# MCU.net
KiCad netlist of a schematic drawn in Altium Designer
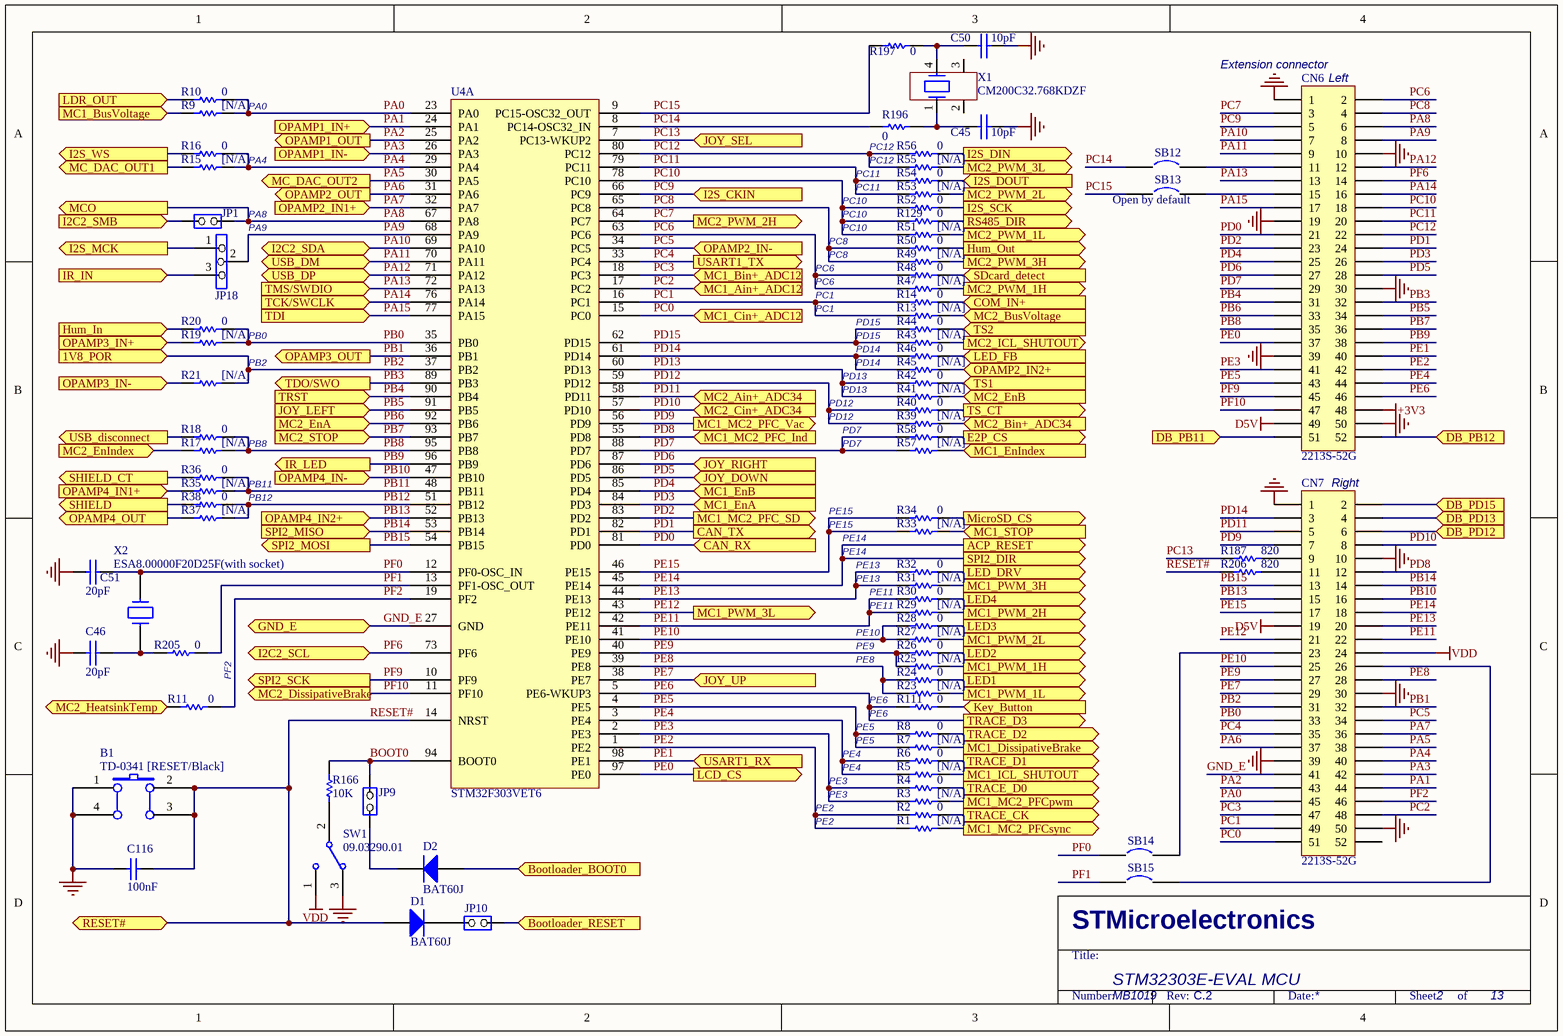
[diagram p0: MCU.SchDoc]

(export (version "E")
  (design (tool "Eeschema 10.0.6"))
  (components
    (comp (ref "B1")
      (value "TD-0341 [RESET/Black]")
      (footprint "PB10")
      (description "SE PUSHBUTTON")
      (libsource (lib "Documents") (part "SW PUSHBUTTON"))
    )
    (comp (ref "C45")
      (value "10pF")
      (footprint "0603C")
      (description "Capacitor")
      (libsource (lib "*") (part "CAP"))
    )
    (comp (ref "C46")
      (value "20pF")
      (footprint "0603C")
      (description "Capacitor")
      (libsource (lib "") (part "CAP_1"))
    )
    (comp (ref "C50")
      (value "10pF")
      (footprint "0603C")
      (description "Capacitor")
      (libsource (lib "*") (part "CAP"))
    )
    (comp (ref "C51")
      (value "20pF")
      (footprint "0603C")
      (description "Capacitor")
      (libsource (lib "") (part "CAP_1"))
    )
    (comp (ref "C116")
      (value "100nF")
      (footprint "0603C")
      (description "Capacitor")
      (fields (field (name "PUBLISHER") "Altium Limited"))
      (libsource (lib "Miscellaneous Devices") (part "CAP"))
    )
    (comp (ref "CN6")
      (value "2213S-52G")
      (footprint "2*26P")
      (description "Header, 26-Pin, Dual row")
      (fields (field (name "PUBLISHER") "Altium Limited"))
      (libsource (lib "MB1019") (part "Header 26X2_1"))
    )
    (comp (ref "CN7")
      (value "2213S-52G")
      (footprint "2*26P")
      (description "Header, 26-Pin, Dual row")
      (fields (field (name "PUBLISHER") "Altium Limited"))
      (libsource (lib "MB1019") (part "Header 26X2_1"))
    )
    (comp (ref "D1")
      (value "BAT60J")
      (footprint "SOD-323")
      (description "Default Diode")
      (fields (field (name "PUBLISHER") "Altium Limited"))
      (libsource (lib "Miscellaneous Devices") (part "Diode"))
    )
    (comp (ref "D2")
      (value "BAT60J")
      (footprint "SOD-323")
      (description "Default Diode")
      (fields (field (name "PUBLISHER") "Altium Limited"))
      (libsource (lib "Miscellaneous Devices") (part "Diode"))
    )
    (comp (ref "JP1") (value "~") (footprint "SIP2") (libsource (lib "*") (part "JP2")))
    (comp (ref "JP9") (value "~") (footprint "SIP2") (libsource (lib "*") (part "JP2")))
    (comp (ref "JP10") (value "~") (footprint "SIP2") (libsource (lib "*") (part "JP2")))
    (comp (ref "JP18") (value "~") (footprint "SIP3") (libsource (lib "STR910_SCHLIB") (part "Jumper3")))
    (comp (ref "R1")
      (value "[N/A]")
      (footprint "0603R")
      (description "Resistor")
      (fields (field (name "PUBLISHER") "Altium Limited"))
      (libsource (lib "Miscellaneous Devices") (part "Res1"))
    )
    (comp (ref "R2")
      (value "0")
      (footprint "0603R")
      (description "Resistor")
      (fields (field (name "PUBLISHER") "Altium Limited"))
      (libsource (lib "Miscellaneous Devices") (part "Res1"))
    )
    (comp (ref "R3")
      (value "[N/A]")
      (footprint "0603R")
      (description "Resistor")
      (fields (field (name "PUBLISHER") "Altium Limited"))
      (libsource (lib "Miscellaneous Devices") (part "Res1"))
    )
    (comp (ref "R4")
      (value "0")
      (footprint "0603R")
      (description "Resistor")
      (fields (field (name "PUBLISHER") "Altium Limited"))
      (libsource (lib "Miscellaneous Devices") (part "Res1"))
    )
    (comp (ref "R5")
      (value "[N/A]")
      (footprint "0603R")
      (description "Resistor")
      (fields (field (name "PUBLISHER") "Altium Limited"))
      (libsource (lib "Miscellaneous Devices") (part "Res1"))
    )
    (comp (ref "R6")
      (value "0")
      (footprint "0603R")
      (description "Resistor")
      (fields (field (name "PUBLISHER") "Altium Limited"))
      (libsource (lib "Miscellaneous Devices") (part "Res1"))
    )
    (comp (ref "R7")
      (value "[N/A]")
      (footprint "0603R")
      (description "Resistor")
      (fields (field (name "PUBLISHER") "Altium Limited"))
      (libsource (lib "Miscellaneous Devices") (part "Res1"))
    )
    (comp (ref "R8")
      (value "0")
      (footprint "0603R")
      (description "Resistor")
      (fields (field (name "PUBLISHER") "Altium Limited"))
      (libsource (lib "Miscellaneous Devices") (part "Res1"))
    )
    (comp (ref "R9")
      (value "[N/A]")
      (footprint "0603R")
      (description "Resistor")
      (fields (field (name "PUBLISHER") "Altium Limited"))
      (libsource (lib "Miscellaneous Devices") (part "Res1"))
    )
    (comp (ref "R10")
      (value "0")
      (footprint "0603R")
      (description "Resistor")
      (fields (field (name "PUBLISHER") "Altium Limited"))
      (libsource (lib "Miscellaneous Devices") (part "Res1"))
    )
    (comp (ref "R11")
      (value "0")
      (footprint "0603R")
      (description "Resistor")
      (fields (field (name "PUBLISHER") "Altium Limited"))
      (libsource (lib "Miscellaneous Devices") (part "Res1"))
    )
    (comp (ref "R13")
      (value "[N/A]")
      (footprint "0603R")
      (description "Resistor")
      (fields (field (name "PUBLISHER") "Altium Limited"))
      (libsource (lib "Miscellaneous Devices") (part "Res1"))
    )
    (comp (ref "R14")
      (value "0")
      (footprint "0603R")
      (description "Resistor")
      (fields (field (name "PUBLISHER") "Altium Limited"))
      (libsource (lib "Miscellaneous Devices") (part "Res1"))
    )
    (comp (ref "R15")
      (value "[N/A]")
      (footprint "0603R")
      (description "Resistor")
      (fields (field (name "PUBLISHER") "Altium Limited"))
      (libsource (lib "Miscellaneous Devices") (part "Res1"))
    )
    (comp (ref "R16")
      (value "0")
      (footprint "0603R")
      (description "Resistor")
      (fields (field (name "PUBLISHER") "Altium Limited"))
      (libsource (lib "Miscellaneous Devices") (part "Res1"))
    )
    (comp (ref "R17")
      (value "[N/A]")
      (footprint "0603R")
      (description "Resistor")
      (fields (field (name "PUBLISHER") "Altium Limited"))
      (libsource (lib "Miscellaneous Devices") (part "Res1"))
    )
    (comp (ref "R18")
      (value "0")
      (footprint "0603R")
      (description "Resistor")
      (fields (field (name "PUBLISHER") "Altium Limited"))
      (libsource (lib "Miscellaneous Devices") (part "Res1"))
    )
    (comp (ref "R19")
      (value "[N/A]")
      (footprint "0603R")
      (description "Resistor")
      (fields (field (name "PUBLISHER") "Altium Limited"))
      (libsource (lib "Miscellaneous Devices") (part "Res1"))
    )
    (comp (ref "R20")
      (value "0")
      (footprint "0603R")
      (description "Resistor")
      (fields (field (name "PUBLISHER") "Altium Limited"))
      (libsource (lib "Miscellaneous Devices") (part "Res1"))
    )
    (comp (ref "R21")
      (value "[N/A]")
      (footprint "0603R")
      (description "Resistor")
      (fields (field (name "PUBLISHER") "Altium Limited"))
      (libsource (lib "Miscellaneous Devices") (part "Res1"))
    )
    (comp (ref "R23")
      (value "[N/A]")
      (footprint "0603R")
      (description "Resistor")
      (fields (field (name "PUBLISHER") "Altium Limited"))
      (libsource (lib "Miscellaneous Devices") (part "Res1"))
    )
    (comp (ref "R24")
      (value "0")
      (footprint "0603R")
      (description "Resistor")
      (fields (field (name "PUBLISHER") "Altium Limited"))
      (libsource (lib "Miscellaneous Devices") (part "Res1"))
    )
    (comp (ref "R25")
      (value "[N/A]")
      (footprint "0603R")
      (description "Resistor")
      (fields (field (name "PUBLISHER") "Altium Limited"))
      (libsource (lib "Miscellaneous Devices") (part "Res1"))
    )
    (comp (ref "R26")
      (value "0")
      (footprint "0603R")
      (description "Resistor")
      (fields (field (name "PUBLISHER") "Altium Limited"))
      (libsource (lib "Miscellaneous Devices") (part "Res1"))
    )
    (comp (ref "R27")
      (value "[N/A]")
      (footprint "0603R")
      (description "Resistor")
      (fields (field (name "PUBLISHER") "Altium Limited"))
      (libsource (lib "Miscellaneous Devices") (part "Res1"))
    )
    (comp (ref "R28")
      (value "0")
      (footprint "0603R")
      (description "Resistor")
      (fields (field (name "PUBLISHER") "Altium Limited"))
      (libsource (lib "Miscellaneous Devices") (part "Res1"))
    )
    (comp (ref "R29")
      (value "[N/A]")
      (footprint "0603R")
      (description "Resistor")
      (fields (field (name "PUBLISHER") "Altium Limited"))
      (libsource (lib "Miscellaneous Devices") (part "Res1"))
    )
    (comp (ref "R30")
      (value "0")
      (footprint "0603R")
      (description "Resistor")
      (fields (field (name "PUBLISHER") "Altium Limited"))
      (libsource (lib "Miscellaneous Devices") (part "Res1"))
    )
    (comp (ref "R31")
      (value "[N/A]")
      (footprint "0603R")
      (description "Resistor")
      (fields (field (name "PUBLISHER") "Altium Limited"))
      (libsource (lib "Miscellaneous Devices") (part "Res1"))
    )
    (comp (ref "R32")
      (value "0")
      (footprint "0603R")
      (description "Resistor")
      (fields (field (name "PUBLISHER") "Altium Limited"))
      (libsource (lib "Miscellaneous Devices") (part "Res1"))
    )
    (comp (ref "R33")
      (value "[N/A]")
      (footprint "0603R")
      (description "Resistor")
      (fields (field (name "PUBLISHER") "Altium Limited"))
      (libsource (lib "Miscellaneous Devices") (part "Res1"))
    )
    (comp (ref "R34")
      (value "0")
      (footprint "0603R")
      (description "Resistor")
      (fields (field (name "PUBLISHER") "Altium Limited"))
      (libsource (lib "Miscellaneous Devices") (part "Res1"))
    )
    (comp (ref "R35")
      (value "[N/A]")
      (footprint "0603R")
      (description "Resistor")
      (fields (field (name "PUBLISHER") "Altium Limited"))
      (libsource (lib "Miscellaneous Devices") (part "Res1"))
    )
    (comp (ref "R36")
      (value "0")
      (footprint "0603R")
      (description "Resistor")
      (fields (field (name "PUBLISHER") "Altium Limited"))
      (libsource (lib "Miscellaneous Devices") (part "Res1"))
    )
    (comp (ref "R37")
      (value "[N/A]")
      (footprint "0603R")
      (description "Resistor")
      (fields (field (name "PUBLISHER") "Altium Limited"))
      (libsource (lib "Miscellaneous Devices") (part "Res1"))
    )
    (comp (ref "R38")
      (value "0")
      (footprint "0603R")
      (description "Resistor")
      (fields (field (name "PUBLISHER") "Altium Limited"))
      (libsource (lib "Miscellaneous Devices") (part "Res1"))
    )
    (comp (ref "R39")
      (value "[N/A]")
      (footprint "0603R")
      (description "Resistor")
      (fields (field (name "PUBLISHER") "Altium Limited"))
      (libsource (lib "Miscellaneous Devices") (part "Res1"))
    )
    (comp (ref "R40")
      (value "0")
      (footprint "0603R")
      (description "Resistor")
      (fields (field (name "PUBLISHER") "Altium Limited"))
      (libsource (lib "Miscellaneous Devices") (part "Res1"))
    )
    (comp (ref "R41")
      (value "[N/A]")
      (footprint "0603R")
      (description "Resistor")
      (fields (field (name "PUBLISHER") "Altium Limited"))
      (libsource (lib "Miscellaneous Devices") (part "Res1"))
    )
    (comp (ref "R42")
      (value "0")
      (footprint "0603R")
      (description "Resistor")
      (fields (field (name "PUBLISHER") "Altium Limited"))
      (libsource (lib "Miscellaneous Devices") (part "Res1"))
    )
    (comp (ref "R43")
      (value "[N/A]")
      (footprint "0603R")
      (description "Resistor")
      (fields (field (name "PUBLISHER") "Altium Limited"))
      (libsource (lib "Miscellaneous Devices") (part "Res1"))
    )
    (comp (ref "R44")
      (value "0")
      (footprint "0603R")
      (description "Resistor")
      (fields (field (name "PUBLISHER") "Altium Limited"))
      (libsource (lib "Miscellaneous Devices") (part "Res1"))
    )
    (comp (ref "R45")
      (value "[N/A]")
      (footprint "0603R")
      (description "Resistor")
      (fields (field (name "PUBLISHER") "Altium Limited"))
      (libsource (lib "Miscellaneous Devices") (part "Res1"))
    )
    (comp (ref "R46")
      (value "0")
      (footprint "0603R")
      (description "Resistor")
      (fields (field (name "PUBLISHER") "Altium Limited"))
      (libsource (lib "Miscellaneous Devices") (part "Res1"))
    )
    (comp (ref "R47")
      (value "[N/A]")
      (footprint "0603R")
      (description "Resistor")
      (fields (field (name "PUBLISHER") "Altium Limited"))
      (libsource (lib "Miscellaneous Devices") (part "Res1"))
    )
    (comp (ref "R48")
      (value "0")
      (footprint "0603R")
      (description "Resistor")
      (fields (field (name "PUBLISHER") "Altium Limited"))
      (libsource (lib "Miscellaneous Devices") (part "Res1"))
    )
    (comp (ref "R49")
      (value "[N/A]")
      (footprint "0603R")
      (description "Resistor")
      (fields (field (name "PUBLISHER") "Altium Limited"))
      (libsource (lib "Miscellaneous Devices") (part "Res1"))
    )
    (comp (ref "R50")
      (value "0")
      (footprint "0603R")
      (description "Resistor")
      (fields (field (name "PUBLISHER") "Altium Limited"))
      (libsource (lib "Miscellaneous Devices") (part "Res1"))
    )
    (comp (ref "R51")
      (value "[N/A]")
      (footprint "0603R")
      (description "Resistor")
      (fields (field (name "PUBLISHER") "Altium Limited"))
      (libsource (lib "Miscellaneous Devices") (part "Res1"))
    )
    (comp (ref "R52")
      (value "0")
      (footprint "0603R")
      (description "Resistor")
      (fields (field (name "PUBLISHER") "Altium Limited"))
      (libsource (lib "Miscellaneous Devices") (part "Res1"))
    )
    (comp (ref "R53")
      (value "[N/A]")
      (footprint "0603R")
      (description "Resistor")
      (fields (field (name "PUBLISHER") "Altium Limited"))
      (libsource (lib "Miscellaneous Devices") (part "Res1"))
    )
    (comp (ref "R54")
      (value "0")
      (footprint "0603R")
      (description "Resistor")
      (fields (field (name "PUBLISHER") "Altium Limited"))
      (libsource (lib "Miscellaneous Devices") (part "Res1"))
    )
    (comp (ref "R55")
      (value "[N/A]")
      (footprint "0603R")
      (description "Resistor")
      (fields (field (name "PUBLISHER") "Altium Limited"))
      (libsource (lib "Miscellaneous Devices") (part "Res1"))
    )
    (comp (ref "R56")
      (value "0")
      (footprint "0603R")
      (description "Resistor")
      (fields (field (name "PUBLISHER") "Altium Limited"))
      (libsource (lib "Miscellaneous Devices") (part "Res1"))
    )
    (comp (ref "R57")
      (value "[N/A]")
      (footprint "0603R")
      (description "Resistor")
      (fields (field (name "PUBLISHER") "Altium Limited"))
      (libsource (lib "Miscellaneous Devices") (part "Res1"))
    )
    (comp (ref "R58")
      (value "0")
      (footprint "0603R")
      (description "Resistor")
      (fields (field (name "PUBLISHER") "Altium Limited"))
      (libsource (lib "Miscellaneous Devices") (part "Res1"))
    )
    (comp (ref "R111")
      (value "0")
      (footprint "0603R")
      (description "Resistor")
      (fields (field (name "PUBLISHER") "Altium Limited"))
      (libsource (lib "Miscellaneous Devices") (part "Res1"))
    )
    (comp (ref "R129")
      (value "0")
      (footprint "0603R")
      (description "Resistor")
      (fields (field (name "PUBLISHER") "Altium Limited"))
      (libsource (lib "Miscellaneous Devices") (part "Res1"))
    )
    (comp (ref "R166")
      (value "10K")
      (footprint "0603R")
      (description "Resistor")
      (fields (field (name "PUBLISHER") "Altium Limited"))
      (libsource (lib "Miscellaneous Devices") (part "res1"))
    )
    (comp (ref "R187")
      (value "820")
      (footprint "0603R")
      (description "Resistor")
      (fields (field (name "PUBLISHER") "Altium Limited"))
      (libsource (lib "Miscellaneous Devices") (part "Res1"))
    )
    (comp (ref "R196")
      (value "0")
      (footprint "0603R")
      (description "Resistor")
      (fields (field (name "PUBLISHER") "Altium Limited"))
      (libsource (lib "Miscellaneous Devices") (part "Res1"))
    )
    (comp (ref "R197")
      (value "0")
      (footprint "0603R")
      (description "Resistor")
      (fields (field (name "PUBLISHER") "Altium Limited"))
      (libsource (lib "Miscellaneous Devices") (part "Res1"))
    )
    (comp (ref "R205")
      (value "0")
      (footprint "0603R")
      (description "Resistor")
      (fields (field (name "PUBLISHER") "Altium Limited"))
      (libsource (lib "Miscellaneous Devices") (part "Res1"))
    )
    (comp (ref "R206")
      (value "820")
      (footprint "0603R")
      (description "Resistor")
      (fields (field (name "PUBLISHER") "Altium Limited"))
      (libsource (lib "Miscellaneous Devices") (part "Res1"))
    )
    (comp (ref "SB12")
      (value "~")
      (footprint "JP2_SMD")
      (description "Circuit Breaker")
      (fields (field (name "PUBLISHER") "Altium Limited"))
      (libsource (lib "Miscellaneous Devices") (part "Circuit Breaker"))
    )
    (comp (ref "SB13")
      (value "~")
      (footprint "JP2_SMD")
      (description "Circuit Breaker")
      (fields (field (name "PUBLISHER") "Altium Limited"))
      (libsource (lib "Miscellaneous Devices") (part "Circuit Breaker"))
    )
    (comp (ref "SB14")
      (value "~")
      (footprint "JP2_SMD")
      (description "Circuit Breaker")
      (fields (field (name "PUBLISHER") "Altium Limited"))
      (libsource (lib "Miscellaneous Devices") (part "Circuit Breaker"))
    )
    (comp (ref "SB15")
      (value "~")
      (footprint "JP2_SMD")
      (description "Circuit Breaker")
      (fields (field (name "PUBLISHER") "Altium Limited"))
      (libsource (lib "Miscellaneous Devices") (part "Circuit Breaker"))
    )
    (comp (ref "SW1")
      (value "09.03290.01")
      (footprint "SIP3")
      (description "SPDT Subminiature Toggle Switch, Right Angle Mounting, Vertical Actuation")
      (fields (field (name "PUBLISHER") "Altium Limited"))
      (libsource (lib "Miscellaneous Devices") (part "SW-SPDT"))
    )
    (comp (ref "U4")
      (value "STM32F303VET6")
      (footprint "IC149-100-025-B5")
      (libsource (lib "MB1019") (part "STM32F303VCT6"))
    )
    (comp (ref "X1") (value "CM200C32.768KDZF") (footprint "SM8") (libsource (lib "*") (part "MC306")))
    (comp (ref "X2")
      (value "ESA8.00000F20D25F(with socket)")
      (footprint "XTAL_socket")
      (description "Crystal")
      (libsource (lib "*") (part "CRYSTAL"))
    )
  )
  (nets
    (net (code "1") (name "+3V3") (class "Default")
      (node (ref "CN6") (pin "48") (pinfunction "48_48") (pintype "passive"))
    )
    (net (code "2") (name "/BOOT0") (class "Default")
      (node (ref "JP9") (pin "2") (pinfunction "NO_2") (pintype "passive"))
      (node (ref "R166") (pin "1") (pinfunction "1_1") (pintype "passive"))
      (node (ref "U4") (pin "94") (pinfunction "BOOT0_94") (pintype "passive"))
    )
    (net (code "3") (name "/Bootloader_BOOT0") (class "Default")
      (node (ref "D2") (pin "1") (pinfunction "A_1") (pintype "passive"))
    )
    (net (code "4") (name "/Bootloader_RESET") (class "Default")
      (node (ref "JP10") (pin "2") (pinfunction "NO_2") (pintype "passive"))
    )
    (net (code "5") (name "/COM_IN+") (class "Default")
      (node (ref "R14") (pin "1") (pinfunction "1_1") (pintype "passive"))
    )
    (net (code "6") (name "/DB_PB11") (class "Default")
      (node (ref "CN6") (pin "51") (pinfunction "51_51") (pintype "passive"))
    )
    (net (code "7") (name "/DB_PB12") (class "Default")
      (node (ref "CN6") (pin "52") (pinfunction "52_52") (pintype "passive"))
    )
    (net (code "8") (name "/DB_PD12") (class "Default")
      (node (ref "CN7") (pin "6") (pinfunction "6_6") (pintype "passive"))
    )
    (net (code "9") (name "/DB_PD13") (class "Default")
      (node (ref "CN7") (pin "4") (pinfunction "4_4") (pintype "passive"))
    )
    (net (code "10") (name "/DB_PD15") (class "Default")
      (node (ref "CN7") (pin "2") (pinfunction "2_2") (pintype "passive"))
    )
    (net (code "11") (name "/E2P_CS") (class "Default")
      (node (ref "R58") (pin "1") (pinfunction "1_1") (pintype "passive"))
    )
    (net (code "12") (name "/GND_E") (class "Default")
      (node (ref "CN7") (pin "41") (pinfunction "41_41") (pintype "passive"))
      (node (ref "U4") (pin "27") (pinfunction "GND_27") (pintype "passive"))
    )
    (net (code "13") (name "/Hum_In") (class "Default")
      (node (ref "R20") (pin "2") (pinfunction "2_2") (pintype "passive"))
    )
    (net (code "14") (name "/Hum_Out") (class "Default")
      (node (ref "R50") (pin "1") (pinfunction "1_1") (pintype "passive"))
    )
    (net (code "15") (name "/I2C2_SMB") (class "Default")
      (node (ref "JP1") (pin "2") (pinfunction "NO_2") (pintype "passive"))
    )
    (net (code "16") (name "/I2S_DIN") (class "Default")
      (node (ref "R56") (pin "1") (pinfunction "1_1") (pintype "passive"))
    )
    (net (code "17") (name "/I2S_DOUT") (class "Default")
      (node (ref "R54") (pin "1") (pinfunction "1_1") (pintype "passive"))
    )
    (net (code "18") (name "/I2S_MCK") (class "Default") (node (ref "JP18") (pin "1") (pintype "passive")))
    (net (code "19") (name "/I2S_SCK") (class "Default")
      (node (ref "R52") (pin "1") (pinfunction "1_1") (pintype "passive"))
    )
    (net (code "20") (name "/I2S_WS") (class "Default")
      (node (ref "R16") (pin "2") (pinfunction "2_2") (pintype "passive"))
    )
    (net (code "21") (name "/IR_IN") (class "Default") (node (ref "JP18") (pin "3") (pintype "passive")))
    (net (code "22") (name "/Key_Button") (class "Default")
      (node (ref "R111") (pin "1") (pinfunction "1_1") (pintype "passive"))
    )
    (net (code "23") (name "/LDR_OUT") (class "Default")
      (node (ref "R10") (pin "2") (pinfunction "2_2") (pintype "passive"))
    )
    (net (code "24") (name "/LED1") (class "Default")
      (node (ref "R24") (pin "1") (pinfunction "1_1") (pintype "passive"))
    )
    (net (code "25") (name "/LED2") (class "Default")
      (node (ref "R26") (pin "1") (pinfunction "1_1") (pintype "passive"))
    )
    (net (code "26") (name "/LED3") (class "Default")
      (node (ref "R28") (pin "1") (pinfunction "1_1") (pintype "passive"))
    )
    (net (code "27") (name "/LED4") (class "Default")
      (node (ref "R30") (pin "1") (pinfunction "1_1") (pintype "passive"))
    )
    (net (code "28") (name "/LED_DRV") (class "Default")
      (node (ref "R32") (pin "1") (pinfunction "1_1") (pintype "passive"))
    )
    (net (code "29") (name "/LED_FB") (class "Default")
      (node (ref "R46") (pin "1") (pinfunction "1_1") (pintype "passive"))
    )
    (net (code "30") (name "/MC1_BusVoltage") (class "Default")
      (node (ref "R9") (pin "2") (pinfunction "2_2") (pintype "passive"))
    )
    (net (code "31") (name "/MC1_DissipativeBrake") (class "Default")
      (node (ref "R7") (pin "1") (pinfunction "1_1") (pintype "passive"))
    )
    (net (code "32") (name "/MC1_EnIndex") (class "Default")
      (node (ref "R57") (pin "1") (pinfunction "1_1") (pintype "passive"))
    )
    (net (code "33") (name "/MC1_ICL_SHUTOUT") (class "Default")
      (node (ref "R5") (pin "1") (pinfunction "1_1") (pintype "passive"))
    )
    (net (code "34") (name "/MC1_MC2_PFCpwm") (class "Default")
      (node (ref "R3") (pin "1") (pinfunction "1_1") (pintype "passive"))
    )
    (net (code "35") (name "/MC1_MC2_PFCsync") (class "Default")
      (node (ref "R1") (pin "1") (pinfunction "1_1") (pintype "passive"))
    )
    (net (code "36") (name "/MC1_PWM_1H") (class "Default")
      (node (ref "R25") (pin "1") (pinfunction "1_1") (pintype "passive"))
    )
    (net (code "37") (name "/MC1_PWM_1L") (class "Default")
      (node (ref "R23") (pin "1") (pinfunction "1_1") (pintype "passive"))
    )
    (net (code "38") (name "/MC1_PWM_2H") (class "Default")
      (node (ref "R29") (pin "1") (pinfunction "1_1") (pintype "passive"))
    )
    (net (code "39") (name "/MC1_PWM_2L") (class "Default")
      (node (ref "R27") (pin "1") (pinfunction "1_1") (pintype "passive"))
    )
    (net (code "40") (name "/MC1_PWM_3H") (class "Default")
      (node (ref "R31") (pin "1") (pinfunction "1_1") (pintype "passive"))
    )
    (net (code "41") (name "/MC1_STOP") (class "Default")
      (node (ref "R33") (pin "1") (pinfunction "1_1") (pintype "passive"))
    )
    (net (code "42") (name "/MC2_Bin+_ADC34") (class "Default")
      (node (ref "R39") (pin "1") (pinfunction "1_1") (pintype "passive"))
    )
    (net (code "43") (name "/MC2_BusVoltage") (class "Default")
      (node (ref "R13") (pin "1") (pinfunction "1_1") (pintype "passive"))
    )
    (net (code "44") (name "/MC2_EnB") (class "Default")
      (node (ref "R41") (pin "1") (pinfunction "1_1") (pintype "passive"))
    )
    (net (code "45") (name "/MC2_EnIndex") (class "Default")
      (node (ref "R17") (pin "2") (pinfunction "2_2") (pintype "passive"))
    )
    (net (code "46") (name "/MC2_HeatsinkTemp") (class "Default")
      (node (ref "R11") (pin "2") (pinfunction "2_2") (pintype "passive"))
    )
    (net (code "47") (name "/MC2_ICL_SHUTOUT") (class "Default")
      (node (ref "R43") (pin "1") (pinfunction "1_1") (pintype "passive"))
    )
    (net (code "48") (name "/MC2_PWM_1H") (class "Default")
      (node (ref "R47") (pin "1") (pinfunction "1_1") (pintype "passive"))
    )
    (net (code "49") (name "/MC2_PWM_1L") (class "Default")
      (node (ref "R51") (pin "1") (pinfunction "1_1") (pintype "passive"))
    )
    (net (code "50") (name "/MC2_PWM_2L") (class "Default")
      (node (ref "R53") (pin "1") (pinfunction "1_1") (pintype "passive"))
    )
    (net (code "51") (name "/MC2_PWM_3H") (class "Default")
      (node (ref "R49") (pin "1") (pinfunction "1_1") (pintype "passive"))
    )
    (net (code "52") (name "/MC2_PWM_3L") (class "Default")
      (node (ref "R55") (pin "1") (pinfunction "1_1") (pintype "passive"))
    )
    (net (code "53") (name "/MC_DAC_OUT1") (class "Default")
      (node (ref "R15") (pin "2") (pinfunction "2_2") (pintype "passive"))
    )
    (net (code "54") (name "/MicroSD_CS") (class "Default")
      (node (ref "R34") (pin "1") (pinfunction "1_1") (pintype "passive"))
    )
    (net (code "55") (name "/OPAMP2_IN2+") (class "Default")
      (node (ref "R45") (pin "1") (pinfunction "1_1") (pintype "passive"))
    )
    (net (code "56") (name "/OPAMP3_IN+") (class "Default")
      (node (ref "R19") (pin "2") (pinfunction "2_2") (pintype "passive"))
    )
    (net (code "57") (name "/OPAMP3_IN-") (class "Default")
      (node (ref "R21") (pin "2") (pinfunction "2_2") (pintype "passive"))
    )
    (net (code "58") (name "/OPAMP4_IN1+") (class "Default")
      (node (ref "R35") (pin "2") (pinfunction "2_2") (pintype "passive"))
    )
    (net (code "59") (name "/OPAMP4_OUT") (class "Default")
      (node (ref "R37") (pin "2") (pinfunction "2_2") (pintype "passive"))
    )
    (net (code "60") (name "/PA0") (class "Default")
      (node (ref "CN7") (pin "45") (pinfunction "45_45") (pintype "passive"))
      (node (ref "R10") (pin "1") (pinfunction "1_1") (pintype "passive"))
      (node (ref "R9") (pin "1") (pinfunction "1_1") (pintype "passive"))
      (node (ref "U4") (pin "23") (pinfunction "PA0_23") (pintype "passive"))
    )
    (net (code "61") (name "/PA1") (class "Default")
      (node (ref "CN7") (pin "44") (pinfunction "44_44") (pintype "passive"))
      (node (ref "U4") (pin "24") (pinfunction "PA1_24") (pintype "passive"))
    )
    (net (code "62") (name "/PA2") (class "Default")
      (node (ref "CN7") (pin "43") (pinfunction "43_43") (pintype "passive"))
      (node (ref "U4") (pin "25") (pinfunction "PA2_25") (pintype "passive"))
    )
    (net (code "63") (name "/PA3") (class "Default")
      (node (ref "CN7") (pin "42") (pinfunction "42_42") (pintype "passive"))
      (node (ref "U4") (pin "26") (pinfunction "PA3_26") (pintype "passive"))
    )
    (net (code "64") (name "/PA4") (class "Default")
      (node (ref "CN7") (pin "40") (pinfunction "40_40") (pintype "passive"))
      (node (ref "R15") (pin "1") (pinfunction "1_1") (pintype "passive"))
      (node (ref "R16") (pin "1") (pinfunction "1_1") (pintype "passive"))
      (node (ref "U4") (pin "29") (pinfunction "PA4_29") (pintype "passive"))
    )
    (net (code "65") (name "/PA5") (class "Default")
      (node (ref "CN7") (pin "38") (pinfunction "38_38") (pintype "passive"))
      (node (ref "U4") (pin "30") (pinfunction "PA5_30") (pintype "passive"))
    )
    (net (code "66") (name "/PA6") (class "Default")
      (node (ref "CN7") (pin "37") (pinfunction "37_37") (pintype "passive"))
      (node (ref "U4") (pin "31") (pinfunction "PA6_31") (pintype "passive"))
    )
    (net (code "67") (name "/PA7") (class "Default")
      (node (ref "CN7") (pin "36") (pinfunction "36_36") (pintype "passive"))
      (node (ref "U4") (pin "32") (pinfunction "PA7_32") (pintype "passive"))
    )
    (net (code "68") (name "/PA8") (class "Default")
      (node (ref "CN6") (pin "6") (pinfunction "6_6") (pintype "passive"))
      (node (ref "JP1") (pin "1") (pinfunction "COMMON_1") (pintype "passive"))
      (node (ref "U4") (pin "67") (pinfunction "PA8_67") (pintype "passive"))
    )
    (net (code "69") (name "/PA9") (class "Default")
      (node (ref "CN6") (pin "8") (pinfunction "8_8") (pintype "passive"))
      (node (ref "JP18") (pin "2") (pintype "passive"))
      (node (ref "U4") (pin "68") (pinfunction "PA9_68") (pintype "passive"))
    )
    (net (code "70") (name "/PA10") (class "Default")
      (node (ref "CN6") (pin "7") (pinfunction "7_7") (pintype "passive"))
      (node (ref "U4") (pin "69") (pinfunction "PA10_69") (pintype "passive"))
    )
    (net (code "71") (name "/PA11") (class "Default")
      (node (ref "CN6") (pin "9") (pinfunction "9_9") (pintype "passive"))
      (node (ref "U4") (pin "70") (pinfunction "PA11_70") (pintype "passive"))
    )
    (net (code "72") (name "/PA12") (class "Default")
      (node (ref "CN6") (pin "12") (pinfunction "12_12") (pintype "passive"))
      (node (ref "U4") (pin "71") (pinfunction "PA12_71") (pintype "passive"))
    )
    (net (code "73") (name "/PA13") (class "Default")
      (node (ref "CN6") (pin "13") (pinfunction "13_13") (pintype "passive"))
      (node (ref "U4") (pin "72") (pinfunction "PA13_72") (pintype "passive"))
    )
    (net (code "74") (name "/PA14") (class "Default")
      (node (ref "CN6") (pin "16") (pinfunction "16_16") (pintype "passive"))
      (node (ref "U4") (pin "76") (pinfunction "PA14_76") (pintype "passive"))
    )
    (net (code "75") (name "/PA15") (class "Default")
      (node (ref "CN6") (pin "17") (pinfunction "17_17") (pintype "passive"))
      (node (ref "U4") (pin "77") (pinfunction "PA15_77") (pintype "passive"))
    )
    (net (code "76") (name "/PB0") (class "Default")
      (node (ref "CN7") (pin "33") (pinfunction "33_33") (pintype "passive"))
      (node (ref "R19") (pin "1") (pinfunction "1_1") (pintype "passive"))
      (node (ref "R20") (pin "1") (pinfunction "1_1") (pintype "passive"))
      (node (ref "U4") (pin "35") (pinfunction "PB0_35") (pintype "passive"))
    )
    (net (code "77") (name "/PB1") (class "Default")
      (node (ref "CN7") (pin "32") (pinfunction "32_32") (pintype "passive"))
      (node (ref "U4") (pin "36") (pinfunction "PB1_36") (pintype "passive"))
    )
    (net (code "78") (name "/PB2") (class "Default")
      (node (ref "CN7") (pin "31") (pinfunction "31_31") (pintype "passive"))
      (node (ref "R21") (pin "1") (pinfunction "1_1") (pintype "passive"))
      (node (ref "U4") (pin "37") (pinfunction "PB2_37") (pintype "passive"))
    )
    (net (code "79") (name "/PB3") (class "Default")
      (node (ref "CN6") (pin "32") (pinfunction "32_32") (pintype "passive"))
      (node (ref "U4") (pin "89") (pinfunction "PB3_89") (pintype "passive"))
    )
    (net (code "80") (name "/PB4") (class "Default")
      (node (ref "CN6") (pin "31") (pinfunction "31_31") (pintype "passive"))
      (node (ref "U4") (pin "90") (pinfunction "PB4_90") (pintype "passive"))
    )
    (net (code "81") (name "/PB5") (class "Default")
      (node (ref "CN6") (pin "34") (pinfunction "34_34") (pintype "passive"))
      (node (ref "U4") (pin "91") (pinfunction "PB5_91") (pintype "passive"))
    )
    (net (code "82") (name "/PB6") (class "Default")
      (node (ref "CN6") (pin "33") (pinfunction "33_33") (pintype "passive"))
      (node (ref "U4") (pin "92") (pinfunction "PB6_92") (pintype "passive"))
    )
    (net (code "83") (name "/PB7") (class "Default")
      (node (ref "CN6") (pin "36") (pinfunction "36_36") (pintype "passive"))
      (node (ref "U4") (pin "93") (pinfunction "PB7_93") (pintype "passive"))
    )
    (net (code "84") (name "/PB8") (class "Default")
      (node (ref "CN6") (pin "35") (pinfunction "35_35") (pintype "passive"))
      (node (ref "R17") (pin "1") (pinfunction "1_1") (pintype "passive"))
      (node (ref "R18") (pin "1") (pinfunction "1_1") (pintype "passive"))
      (node (ref "U4") (pin "95") (pinfunction "PB8_95") (pintype "passive"))
    )
    (net (code "85") (name "/PB9") (class "Default")
      (node (ref "CN6") (pin "38") (pinfunction "38_38") (pintype "passive"))
      (node (ref "U4") (pin "96") (pinfunction "PB9_96") (pintype "passive"))
    )
    (net (code "86") (name "/PB10") (class "Default")
      (node (ref "CN7") (pin "16") (pinfunction "16_16") (pintype "passive"))
      (node (ref "U4") (pin "47") (pinfunction "PB10_47") (pintype "passive"))
    )
    (net (code "87") (name "/PB11") (class "Default")
      (node (ref "R35") (pin "1") (pinfunction "1_1") (pintype "passive"))
      (node (ref "R36") (pin "1") (pinfunction "1_1") (pintype "passive"))
      (node (ref "U4") (pin "48") (pinfunction "PB11_48") (pintype "passive"))
    )
    (net (code "88") (name "/PB12") (class "Default")
      (node (ref "R37") (pin "1") (pinfunction "1_1") (pintype "passive"))
      (node (ref "R38") (pin "1") (pinfunction "1_1") (pintype "passive"))
      (node (ref "U4") (pin "51") (pinfunction "PB12_51") (pintype "passive"))
    )
    (net (code "89") (name "/PB13") (class "Default")
      (node (ref "CN7") (pin "15") (pinfunction "15_15") (pintype "passive"))
      (node (ref "U4") (pin "52") (pinfunction "PB13_52") (pintype "passive"))
    )
    (net (code "90") (name "/PB14") (class "Default")
      (node (ref "CN7") (pin "14") (pinfunction "14_14") (pintype "passive"))
      (node (ref "U4") (pin "53") (pinfunction "PB14_53") (pintype "passive"))
    )
    (net (code "91") (name "/PB15") (class "Default")
      (node (ref "CN7") (pin "13") (pinfunction "13_13") (pintype "passive"))
      (node (ref "U4") (pin "54") (pinfunction "PB15_54") (pintype "passive"))
    )
    (net (code "92") (name "/PC0") (class "Default")
      (node (ref "CN7") (pin "51") (pinfunction "51_51") (pintype "passive"))
      (node (ref "U4") (pin "15") (pinfunction "PC0_15") (pintype "passive"))
    )
    (net (code "93") (name "/PC1") (class "Default")
      (node (ref "CN7") (pin "49") (pinfunction "49_49") (pintype "passive"))
      (node (ref "R13") (pin "2") (pinfunction "2_2") (pintype "passive"))
      (node (ref "R14") (pin "2") (pinfunction "2_2") (pintype "passive"))
      (node (ref "U4") (pin "16") (pinfunction "PC1_16") (pintype "passive"))
    )
    (net (code "94") (name "/PC2") (class "Default")
      (node (ref "CN7") (pin "48") (pinfunction "48_48") (pintype "passive"))
      (node (ref "U4") (pin "17") (pinfunction "PC2_17") (pintype "passive"))
    )
    (net (code "95") (name "/PC3") (class "Default")
      (node (ref "CN7") (pin "47") (pinfunction "47_47") (pintype "passive"))
      (node (ref "U4") (pin "18") (pinfunction "PC3_18") (pintype "passive"))
    )
    (net (code "96") (name "/PC4") (class "Default")
      (node (ref "CN7") (pin "35") (pinfunction "35_35") (pintype "passive"))
      (node (ref "U4") (pin "33") (pinfunction "PC4_33") (pintype "passive"))
    )
    (net (code "97") (name "/PC5") (class "Default")
      (node (ref "CN7") (pin "34") (pinfunction "34_34") (pintype "passive"))
      (node (ref "U4") (pin "34") (pinfunction "PC5_34") (pintype "passive"))
    )
    (net (code "98") (name "/PC6") (class "Default")
      (node (ref "CN6") (pin "2") (pinfunction "2_2") (pintype "passive"))
      (node (ref "R47") (pin "2") (pinfunction "2_2") (pintype "passive"))
      (node (ref "R48") (pin "2") (pinfunction "2_2") (pintype "passive"))
      (node (ref "U4") (pin "63") (pinfunction "PC6_63") (pintype "passive"))
    )
    (net (code "99") (name "/PC7") (class "Default")
      (node (ref "CN6") (pin "3") (pinfunction "3_3") (pintype "passive"))
      (node (ref "U4") (pin "64") (pinfunction "PC7_64") (pintype "passive"))
    )
    (net (code "100") (name "/PC8") (class "Default")
      (node (ref "CN6") (pin "4") (pinfunction "4_4") (pintype "passive"))
      (node (ref "R49") (pin "2") (pinfunction "2_2") (pintype "passive"))
      (node (ref "R50") (pin "2") (pinfunction "2_2") (pintype "passive"))
      (node (ref "U4") (pin "65") (pinfunction "PC8_65") (pintype "passive"))
    )
    (net (code "101") (name "/PC9") (class "Default")
      (node (ref "CN6") (pin "5") (pinfunction "5_5") (pintype "passive"))
      (node (ref "U4") (pin "66") (pinfunction "PC9_66") (pintype "passive"))
    )
    (net (code "102") (name "/PC10") (class "Default")
      (node (ref "CN6") (pin "18") (pinfunction "18_18") (pintype "passive"))
      (node (ref "R129") (pin "2") (pinfunction "2_2") (pintype "passive"))
      (node (ref "R51") (pin "2") (pinfunction "2_2") (pintype "passive"))
      (node (ref "R52") (pin "2") (pinfunction "2_2") (pintype "passive"))
      (node (ref "U4") (pin "78") (pinfunction "PC10_78") (pintype "passive"))
    )
    (net (code "103") (name "/PC11") (class "Default")
      (node (ref "CN6") (pin "20") (pinfunction "20_20") (pintype "passive"))
      (node (ref "R53") (pin "2") (pinfunction "2_2") (pintype "passive"))
      (node (ref "R54") (pin "2") (pinfunction "2_2") (pintype "passive"))
      (node (ref "U4") (pin "79") (pinfunction "PC11_79") (pintype "passive"))
    )
    (net (code "104") (name "/PC12") (class "Default")
      (node (ref "CN6") (pin "22") (pinfunction "22_22") (pintype "passive"))
      (node (ref "R55") (pin "2") (pinfunction "2_2") (pintype "passive"))
      (node (ref "R56") (pin "2") (pinfunction "2_2") (pintype "passive"))
      (node (ref "U4") (pin "80") (pinfunction "PC12_80") (pintype "passive"))
    )
    (net (code "105") (name "/PC13") (class "Default")
      (node (ref "R187") (pin "1") (pinfunction "1_1") (pintype "passive"))
      (node (ref "U4") (pin "7") (pinfunction "PC13-WKUP2_7") (pintype "passive"))
    )
    (net (code "106") (name "/PC14") (class "Default")
      (node (ref "R196") (pin "2") (pinfunction "2_2") (pintype "passive"))
      (node (ref "SB12") (pin "1") (pinfunction "1_1") (pintype "passive"))
      (node (ref "U4") (pin "8") (pinfunction "PC14-OSC32_IN_8") (pintype "passive"))
    )
    (net (code "107") (name "/PC15") (class "Default")
      (node (ref "R197") (pin "2") (pinfunction "2_2") (pintype "passive"))
      (node (ref "SB13") (pin "1") (pinfunction "1_1") (pintype "passive"))
      (node (ref "U4") (pin "9") (pinfunction "PC15-OSC32_OUT_9") (pintype "passive"))
    )
    (net (code "108") (name "/PD0") (class "Default")
      (node (ref "CN6") (pin "21") (pinfunction "21_21") (pintype "passive"))
      (node (ref "U4") (pin "81") (pinfunction "PD0_81") (pintype "passive"))
    )
    (net (code "109") (name "/PD1") (class "Default")
      (node (ref "CN6") (pin "24") (pinfunction "24_24") (pintype "passive"))
      (node (ref "U4") (pin "82") (pinfunction "PD1_82") (pintype "passive"))
    )
    (net (code "110") (name "/PD2") (class "Default")
      (node (ref "CN6") (pin "23") (pinfunction "23_23") (pintype "passive"))
      (node (ref "U4") (pin "83") (pinfunction "PD2_83") (pintype "passive"))
    )
    (net (code "111") (name "/PD3") (class "Default")
      (node (ref "CN6") (pin "26") (pinfunction "26_26") (pintype "passive"))
      (node (ref "U4") (pin "84") (pinfunction "PD3_84") (pintype "passive"))
    )
    (net (code "112") (name "/PD4") (class "Default")
      (node (ref "CN6") (pin "25") (pinfunction "25_25") (pintype "passive"))
      (node (ref "U4") (pin "85") (pinfunction "PD4_85") (pintype "passive"))
    )
    (net (code "113") (name "/PD5") (class "Default")
      (node (ref "CN6") (pin "28") (pinfunction "28_28") (pintype "passive"))
      (node (ref "U4") (pin "86") (pinfunction "PD5_86") (pintype "passive"))
    )
    (net (code "114") (name "/PD6") (class "Default")
      (node (ref "CN6") (pin "27") (pinfunction "27_27") (pintype "passive"))
      (node (ref "U4") (pin "87") (pinfunction "PD6_87") (pintype "passive"))
    )
    (net (code "115") (name "/PD7") (class "Default")
      (node (ref "CN6") (pin "29") (pinfunction "29_29") (pintype "passive"))
      (node (ref "R57") (pin "2") (pinfunction "2_2") (pintype "passive"))
      (node (ref "R58") (pin "2") (pinfunction "2_2") (pintype "passive"))
      (node (ref "U4") (pin "88") (pinfunction "PD7_88") (pintype "passive"))
    )
    (net (code "116") (name "/PD8") (class "Default")
      (node (ref "CN7") (pin "12") (pinfunction "12_12") (pintype "passive"))
      (node (ref "U4") (pin "55") (pinfunction "PD8_55") (pintype "passive"))
    )
    (net (code "117") (name "/PD9") (class "Default")
      (node (ref "CN7") (pin "7") (pinfunction "7_7") (pintype "passive"))
      (node (ref "U4") (pin "56") (pinfunction "PD9_56") (pintype "passive"))
    )
    (net (code "118") (name "/PD10") (class "Default")
      (node (ref "CN7") (pin "8") (pinfunction "8_8") (pintype "passive"))
      (node (ref "U4") (pin "57") (pinfunction "PD10_57") (pintype "passive"))
    )
    (net (code "119") (name "/PD11") (class "Default")
      (node (ref "CN7") (pin "5") (pinfunction "5_5") (pintype "passive"))
      (node (ref "U4") (pin "58") (pinfunction "PD11_58") (pintype "passive"))
    )
    (net (code "120") (name "/PD12") (class "Default")
      (node (ref "R39") (pin "2") (pinfunction "2_2") (pintype "passive"))
      (node (ref "R40") (pin "2") (pinfunction "2_2") (pintype "passive"))
      (node (ref "U4") (pin "59") (pinfunction "PD12_59") (pintype "passive"))
    )
    (net (code "121") (name "/PD13") (class "Default")
      (node (ref "R41") (pin "2") (pinfunction "2_2") (pintype "passive"))
      (node (ref "R42") (pin "2") (pinfunction "2_2") (pintype "passive"))
      (node (ref "U4") (pin "60") (pinfunction "PD13_60") (pintype "passive"))
    )
    (net (code "122") (name "/PD14") (class "Default")
      (node (ref "CN7") (pin "3") (pinfunction "3_3") (pintype "passive"))
      (node (ref "R45") (pin "2") (pinfunction "2_2") (pintype "passive"))
      (node (ref "R46") (pin "2") (pinfunction "2_2") (pintype "passive"))
      (node (ref "U4") (pin "61") (pinfunction "PD14_61") (pintype "passive"))
    )
    (net (code "123") (name "/PD15") (class "Default")
      (node (ref "R43") (pin "2") (pinfunction "2_2") (pintype "passive"))
      (node (ref "R44") (pin "2") (pinfunction "2_2") (pintype "passive"))
      (node (ref "U4") (pin "62") (pinfunction "PD15_62") (pintype "passive"))
    )
    (net (code "124") (name "/PE0") (class "Default")
      (node (ref "CN6") (pin "37") (pinfunction "37_37") (pintype "passive"))
      (node (ref "U4") (pin "97") (pinfunction "PE0_97") (pintype "passive"))
    )
    (net (code "125") (name "/PE1") (class "Default")
      (node (ref "CN6") (pin "40") (pinfunction "40_40") (pintype "passive"))
      (node (ref "U4") (pin "98") (pinfunction "PE1_98") (pintype "passive"))
    )
    (net (code "126") (name "/PE2") (class "Default")
      (node (ref "CN6") (pin "42") (pinfunction "42_42") (pintype "passive"))
      (node (ref "R1") (pin "2") (pinfunction "2_2") (pintype "passive"))
      (node (ref "R2") (pin "2") (pinfunction "2_2") (pintype "passive"))
      (node (ref "U4") (pin "1") (pinfunction "PE2_1") (pintype "passive"))
    )
    (net (code "127") (name "/PE3") (class "Default")
      (node (ref "CN6") (pin "41") (pinfunction "41_41") (pintype "passive"))
      (node (ref "R3") (pin "2") (pinfunction "2_2") (pintype "passive"))
      (node (ref "R4") (pin "2") (pinfunction "2_2") (pintype "passive"))
      (node (ref "U4") (pin "2") (pinfunction "PE3_2") (pintype "passive"))
    )
    (net (code "128") (name "/PE4") (class "Default")
      (node (ref "CN6") (pin "44") (pinfunction "44_44") (pintype "passive"))
      (node (ref "R5") (pin "2") (pinfunction "2_2") (pintype "passive"))
      (node (ref "R6") (pin "2") (pinfunction "2_2") (pintype "passive"))
      (node (ref "U4") (pin "3") (pinfunction "PE4_3") (pintype "passive"))
    )
    (net (code "129") (name "/PE5") (class "Default")
      (node (ref "CN6") (pin "43") (pinfunction "43_43") (pintype "passive"))
      (node (ref "R7") (pin "2") (pinfunction "2_2") (pintype "passive"))
      (node (ref "R8") (pin "2") (pinfunction "2_2") (pintype "passive"))
      (node (ref "U4") (pin "4") (pinfunction "PE5_4") (pintype "passive"))
    )
    (net (code "130") (name "/PE6") (class "Default")
      (node (ref "CN6") (pin "46") (pinfunction "46_46") (pintype "passive"))
      (node (ref "R111") (pin "2") (pinfunction "2_2") (pintype "passive"))
      (node (ref "U4") (pin "5") (pinfunction "PE6-WKUP3_5") (pintype "passive"))
    )
    (net (code "131") (name "/PE7") (class "Default")
      (node (ref "CN7") (pin "29") (pinfunction "29_29") (pintype "passive"))
      (node (ref "U4") (pin "38") (pinfunction "PE7_38") (pintype "passive"))
    )
    (net (code "132") (name "/PE8") (class "Default")
      (node (ref "CN7") (pin "28") (pinfunction "28_28") (pintype "passive"))
      (node (ref "R23") (pin "2") (pinfunction "2_2") (pintype "passive"))
      (node (ref "R24") (pin "2") (pinfunction "2_2") (pintype "passive"))
      (node (ref "U4") (pin "39") (pinfunction "PE8_39") (pintype "passive"))
    )
    (net (code "133") (name "/PE9") (class "Default")
      (node (ref "CN7") (pin "27") (pinfunction "27_27") (pintype "passive"))
      (node (ref "R25") (pin "2") (pinfunction "2_2") (pintype "passive"))
      (node (ref "R26") (pin "2") (pinfunction "2_2") (pintype "passive"))
      (node (ref "U4") (pin "40") (pinfunction "PE9_40") (pintype "passive"))
    )
    (net (code "134") (name "/PE10") (class "Default")
      (node (ref "CN7") (pin "25") (pinfunction "25_25") (pintype "passive"))
      (node (ref "R27") (pin "2") (pinfunction "2_2") (pintype "passive"))
      (node (ref "R28") (pin "2") (pinfunction "2_2") (pintype "passive"))
      (node (ref "U4") (pin "41") (pinfunction "PE10_41") (pintype "passive"))
    )
    (net (code "135") (name "/PE11") (class "Default")
      (node (ref "CN7") (pin "22") (pinfunction "22_22") (pintype "passive"))
      (node (ref "R29") (pin "2") (pinfunction "2_2") (pintype "passive"))
      (node (ref "R30") (pin "2") (pinfunction "2_2") (pintype "passive"))
      (node (ref "U4") (pin "42") (pinfunction "PE11_42") (pintype "passive"))
    )
    (net (code "136") (name "/PE12") (class "Default")
      (node (ref "CN7") (pin "21") (pinfunction "21_21") (pintype "passive"))
      (node (ref "U4") (pin "43") (pinfunction "PE12_43") (pintype "passive"))
    )
    (net (code "137") (name "/PE13") (class "Default")
      (node (ref "CN7") (pin "20") (pinfunction "20_20") (pintype "passive"))
      (node (ref "R31") (pin "2") (pinfunction "2_2") (pintype "passive"))
      (node (ref "R32") (pin "2") (pinfunction "2_2") (pintype "passive"))
      (node (ref "U4") (pin "44") (pinfunction "PE13_44") (pintype "passive"))
    )
    (net (code "138") (name "/PE14") (class "Default")
      (node (ref "CN7") (pin "18") (pinfunction "18_18") (pintype "passive"))
      (node (ref "U4") (pin "45") (pinfunction "PE14_45") (pintype "passive"))
    )
    (net (code "139") (name "/PE15") (class "Default")
      (node (ref "CN7") (pin "17") (pinfunction "17_17") (pintype "passive"))
      (node (ref "R33") (pin "2") (pinfunction "2_2") (pintype "passive"))
      (node (ref "R34") (pin "2") (pinfunction "2_2") (pintype "passive"))
      (node (ref "U4") (pin "46") (pinfunction "PE15_46") (pintype "passive"))
    )
    (net (code "140") (name "/PF0") (class "Default")
      (node (ref "C51") (pin "1") (pinfunction "1_1") (pintype "passive"))
      (node (ref "SB14") (pin "1") (pinfunction "1_1") (pintype "passive"))
      (node (ref "U4") (pin "12") (pinfunction "PF0-OSC_IN_12") (pintype "passive"))
      (node (ref "X2") (pin "2") (pinfunction "2_2") (pintype "passive"))
    )
    (net (code "141") (name "/PF1") (class "Default")
      (node (ref "R205") (pin "1") (pinfunction "1_1") (pintype "passive"))
      (node (ref "SB15") (pin "1") (pinfunction "1_1") (pintype "passive"))
      (node (ref "U4") (pin "13") (pinfunction "PF1-OSC_OUT_13") (pintype "passive"))
    )
    (net (code "142") (name "/PF2") (class "Default")
      (node (ref "CN7") (pin "46") (pinfunction "46_46") (pintype "passive"))
      (node (ref "R11") (pin "1") (pinfunction "1_1") (pintype "passive"))
      (node (ref "U4") (pin "19") (pinfunction "PF2_19") (pintype "passive"))
    )
    (net (code "143") (name "/PF6") (class "Default")
      (node (ref "CN6") (pin "14") (pinfunction "14_14") (pintype "passive"))
      (node (ref "U4") (pin "73") (pinfunction "PF6_73") (pintype "passive"))
    )
    (net (code "144") (name "/PF9") (class "Default")
      (node (ref "CN6") (pin "45") (pinfunction "45_45") (pintype "passive"))
      (node (ref "U4") (pin "10") (pinfunction "PF9_10") (pintype "passive"))
    )
    (net (code "145") (name "/PF10") (class "Default")
      (node (ref "CN6") (pin "47") (pinfunction "47_47") (pintype "passive"))
      (node (ref "U4") (pin "11") (pinfunction "PF10_11") (pintype "passive"))
    )
    (net (code "146") (name "/RESET#") (class "Default")
      (node (ref "B1") (pin "2") (pinfunction "B0_2") (pintype "passive"))
      (node (ref "B1") (pin "3") (pinfunction "B1_3") (pintype "passive"))
      (node (ref "C116") (pin "2") (pinfunction "2_2") (pintype "passive"))
      (node (ref "D1") (pin "1") (pinfunction "A_1") (pintype "passive"))
      (node (ref "R206") (pin "2") (pinfunction "2_2") (pintype "passive"))
      (node (ref "U4") (pin "14") (pinfunction "NRST_14") (pintype "passive"))
    )
    (net (code "147") (name "/RS485_DIR") (class "Default")
      (node (ref "R129") (pin "1") (pinfunction "1_1") (pintype "passive"))
    )
    (net (code "148") (name "/SDcard_detect") (class "Default")
      (node (ref "R48") (pin "1") (pinfunction "1_1") (pintype "passive"))
    )
    (net (code "149") (name "/SHIELD") (class "Default")
      (node (ref "R38") (pin "2") (pinfunction "2_2") (pintype "passive"))
    )
    (net (code "150") (name "/SHIELD_CT") (class "Default")
      (node (ref "R36") (pin "2") (pinfunction "2_2") (pintype "passive"))
    )
    (net (code "151") (name "/TRACE_CK") (class "Default")
      (node (ref "R2") (pin "1") (pinfunction "1_1") (pintype "passive"))
    )
    (net (code "152") (name "/TRACE_D0") (class "Default")
      (node (ref "R4") (pin "1") (pinfunction "1_1") (pintype "passive"))
    )
    (net (code "153") (name "/TRACE_D1") (class "Default")
      (node (ref "R6") (pin "1") (pinfunction "1_1") (pintype "passive"))
    )
    (net (code "154") (name "/TRACE_D2") (class "Default")
      (node (ref "R8") (pin "1") (pinfunction "1_1") (pintype "passive"))
    )
    (net (code "155") (name "/TS1") (class "Default")
      (node (ref "R42") (pin "1") (pinfunction "1_1") (pintype "passive"))
    )
    (net (code "156") (name "/TS2") (class "Default")
      (node (ref "R44") (pin "1") (pinfunction "1_1") (pintype "passive"))
    )
    (net (code "157") (name "/TS_CT") (class "Default")
      (node (ref "R40") (pin "1") (pinfunction "1_1") (pintype "passive"))
    )
    (net (code "158") (name "/USB_disconnect") (class "Default")
      (node (ref "R18") (pin "2") (pinfunction "2_2") (pintype "passive"))
    )
    (net (code "159") (name "D5V") (class "Default")
      (node (ref "CN6") (pin "49") (pinfunction "49_49") (pintype "passive"))
      (node (ref "CN7") (pin "19") (pinfunction "19_19") (pintype "passive"))
    )
    (net (code "160") (name "GND") (class "Default")
      (node (ref "B1") (pin "1") (pinfunction "A0_1") (pintype "passive"))
      (node (ref "B1") (pin "4") (pinfunction "A1_4") (pintype "passive"))
      (node (ref "C116") (pin "1") (pinfunction "1_1") (pintype "passive"))
      (node (ref "C45") (pin "2") (pinfunction "2_2") (pintype "passive"))
      (node (ref "C46") (pin "2") (pinfunction "2_2") (pintype "passive"))
      (node (ref "C50") (pin "2") (pinfunction "2_2") (pintype "passive"))
      (node (ref "C51") (pin "2") (pinfunction "2_2") (pintype "passive"))
      (node (ref "CN6") (pin "1") (pinfunction "1_1") (pintype "passive"))
      (node (ref "CN6") (pin "10") (pinfunction "10_10") (pintype "passive"))
      (node (ref "CN6") (pin "19") (pinfunction "19_19") (pintype "passive"))
      (node (ref "CN6") (pin "30") (pinfunction "30_30") (pintype "passive"))
      (node (ref "CN6") (pin "39") (pinfunction "39_39") (pintype "passive"))
      (node (ref "CN6") (pin "50") (pinfunction "50_50") (pintype "passive"))
      (node (ref "CN7") (pin "1") (pinfunction "1_1") (pintype "passive"))
      (node (ref "CN7") (pin "10") (pinfunction "10_10") (pintype "passive"))
      (node (ref "CN7") (pin "30") (pinfunction "30_30") (pintype "passive"))
      (node (ref "CN7") (pin "39") (pinfunction "39_39") (pintype "passive"))
      (node (ref "CN7") (pin "50") (pinfunction "50_50") (pintype "passive"))
      (node (ref "SW1") (pin "3") (pintype "passive"))
    )
    (net (code "161") (name "Net-(C45-Pad1)") (class "Default")
      (node (ref "C45") (pin "1") (pinfunction "1_1") (pintype "passive"))
      (node (ref "R196") (pin "1") (pinfunction "1_1") (pintype "passive"))
      (node (ref "X1") (pin "1") (pinfunction "1_1") (pintype "passive"))
    )
    (net (code "162") (name "Net-(C46-Pad1)") (class "Default")
      (node (ref "C46") (pin "1") (pinfunction "1_1") (pintype "passive"))
      (node (ref "R205") (pin "2") (pinfunction "2_2") (pintype "passive"))
      (node (ref "X2") (pin "1") (pinfunction "1_1") (pintype "passive"))
    )
    (net (code "163") (name "Net-(C50-Pad1)") (class "Default")
      (node (ref "C50") (pin "1") (pinfunction "1_1") (pintype "passive"))
      (node (ref "R197") (pin "1") (pinfunction "1_1") (pintype "passive"))
      (node (ref "X1") (pin "4") (pinfunction "4_4") (pintype "passive"))
    )
    (net (code "164") (name "Net-(CN6-Pad11)") (class "Default")
      (node (ref "CN6") (pin "11") (pinfunction "11_11") (pintype "passive"))
      (node (ref "SB12") (pin "2") (pinfunction "2_2") (pintype "passive"))
    )
    (net (code "165") (name "Net-(CN6-Pad15)") (class "Default")
      (node (ref "CN6") (pin "15") (pinfunction "15_15") (pintype "passive"))
      (node (ref "SB13") (pin "2") (pinfunction "2_2") (pintype "passive"))
    )
    (net (code "166") (name "Net-(CN7-Pad9)") (class "Default")
      (node (ref "CN7") (pin "9") (pinfunction "9_9") (pintype "passive"))
      (node (ref "R187") (pin "2") (pinfunction "2_2") (pintype "passive"))
    )
    (net (code "167") (name "Net-(CN7-Pad11)") (class "Default")
      (node (ref "CN7") (pin "11") (pinfunction "11_11") (pintype "passive"))
      (node (ref "R206") (pin "1") (pinfunction "1_1") (pintype "passive"))
    )
    (net (code "168") (name "Net-(CN7-Pad23)") (class "Default")
      (node (ref "CN7") (pin "23") (pinfunction "23_23") (pintype "passive"))
      (node (ref "SB14") (pin "2") (pinfunction "2_2") (pintype "passive"))
    )
    (net (code "169") (name "Net-(CN7-Pad26)") (class "Default")
      (node (ref "CN7") (pin "26") (pinfunction "26_26") (pintype "passive"))
      (node (ref "SB15") (pin "2") (pinfunction "2_2") (pintype "passive"))
    )
    (net (code "170") (name "Net-(D1-K)") (class "Default")
      (node (ref "D1") (pin "2") (pinfunction "K_2") (pintype "passive"))
      (node (ref "JP10") (pin "1") (pinfunction "COMMON_1") (pintype "passive"))
    )
    (net (code "171") (name "Net-(D2-K)") (class "Default")
      (node (ref "D2") (pin "2") (pinfunction "K_2") (pintype "passive"))
      (node (ref "JP9") (pin "1") (pinfunction "COMMON_1") (pintype "passive"))
    )
    (net (code "172") (name "Net-(R166-Pad2)") (class "Default")
      (node (ref "R166") (pin "2") (pinfunction "2_2") (pintype "passive"))
      (node (ref "SW1") (pin "2") (pintype "passive"))
    )
    (net (code "173") (name "VDD") (class "Default")
      (node (ref "CN7") (pin "24") (pinfunction "24_24") (pintype "passive"))
      (node (ref "SW1") (pin "1") (pintype "passive"))
    )
    (net (code "174") (name "unconnected-(CN7-Pad52)") (class "Default")
      (node (ref "CN7") (pin "52") (pinfunction "52_52") (pintype "passive"))
    )
    (net (code "175") (name "unconnected-(X1-Pad2)") (class "Default")
      (node (ref "X1") (pin "2") (pinfunction "2_2") (pintype "passive"))
    )
    (net (code "176") (name "unconnected-(X1-Pad3)") (class "Default")
      (node (ref "X1") (pin "3") (pinfunction "3_3") (pintype "passive"))
    )
  )
)
